# Combined_MXP_board.net
KiCad netlist of a schematic drawn in EAGLE
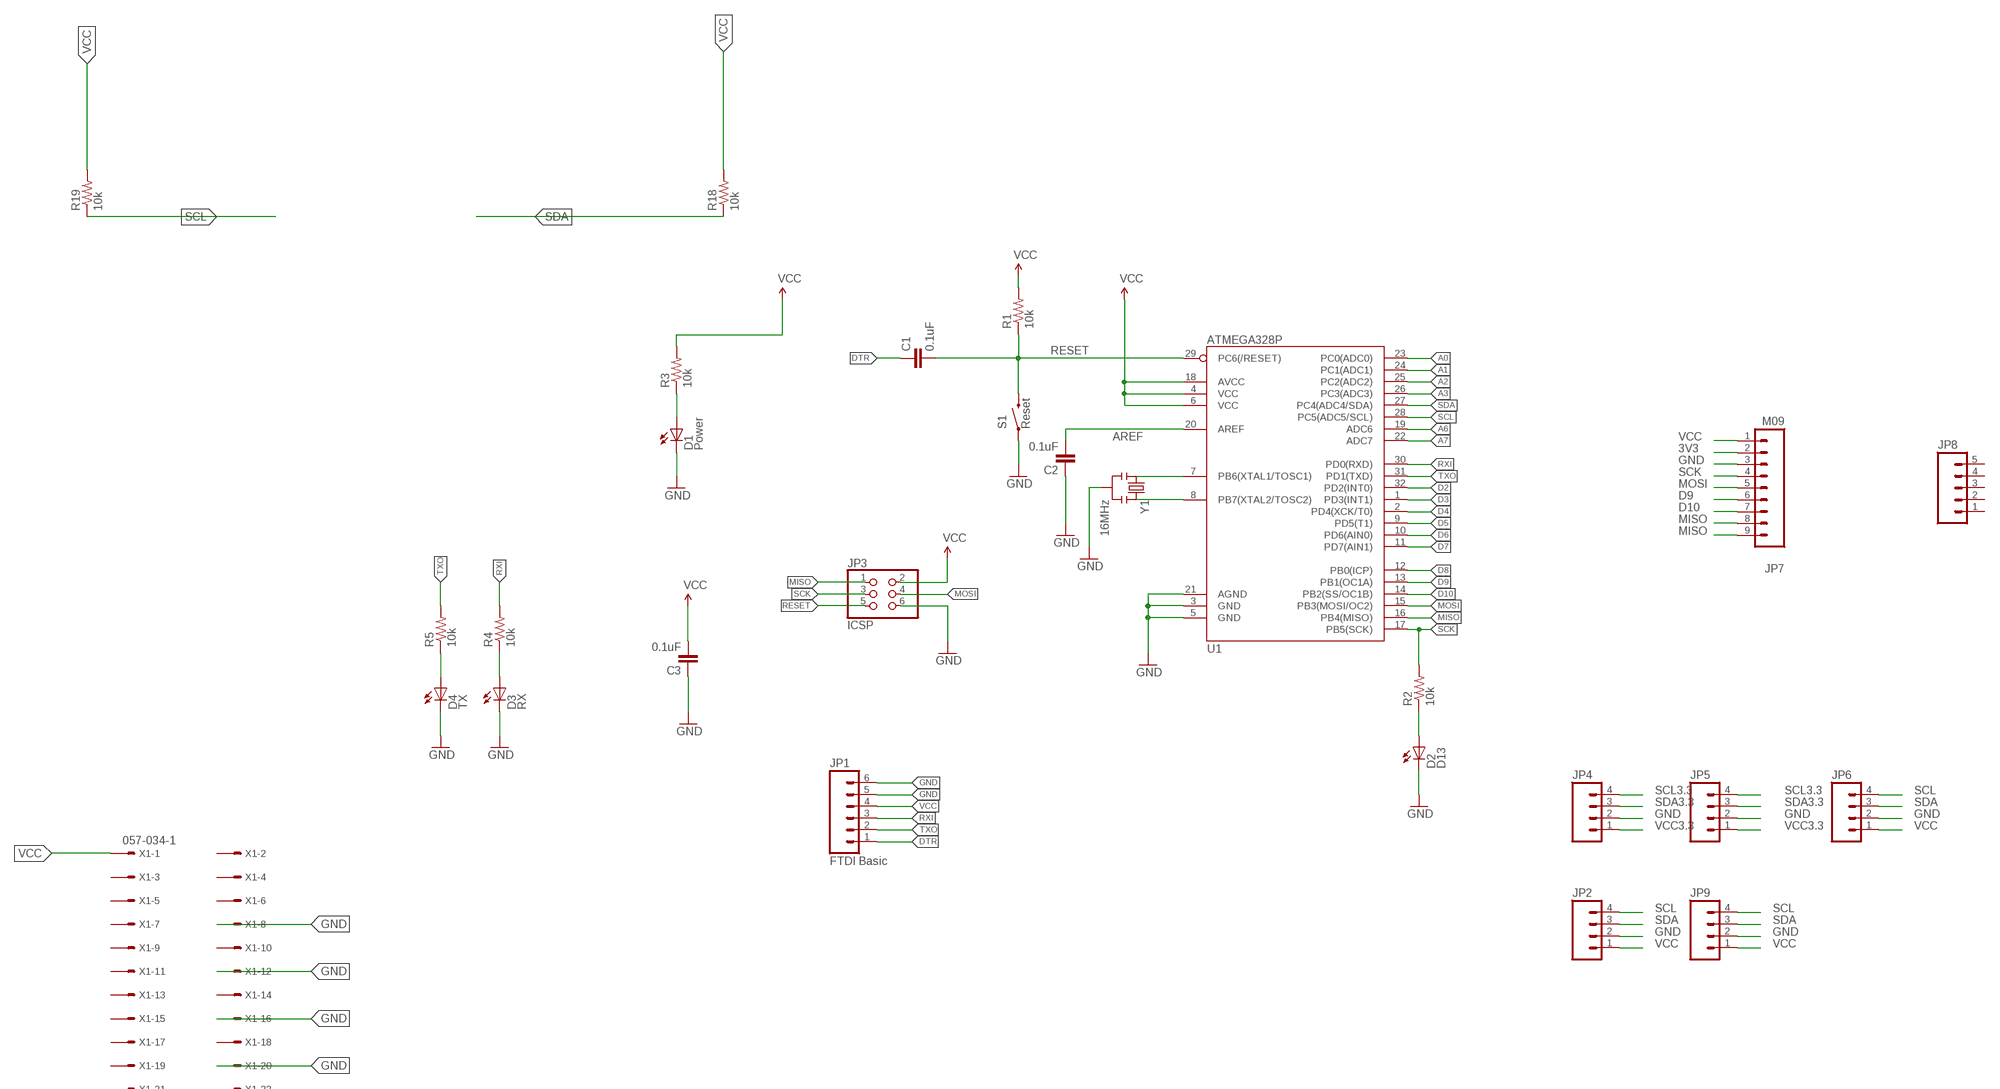
[diagram p0: schematic, sheet 1, part 1 of 2]
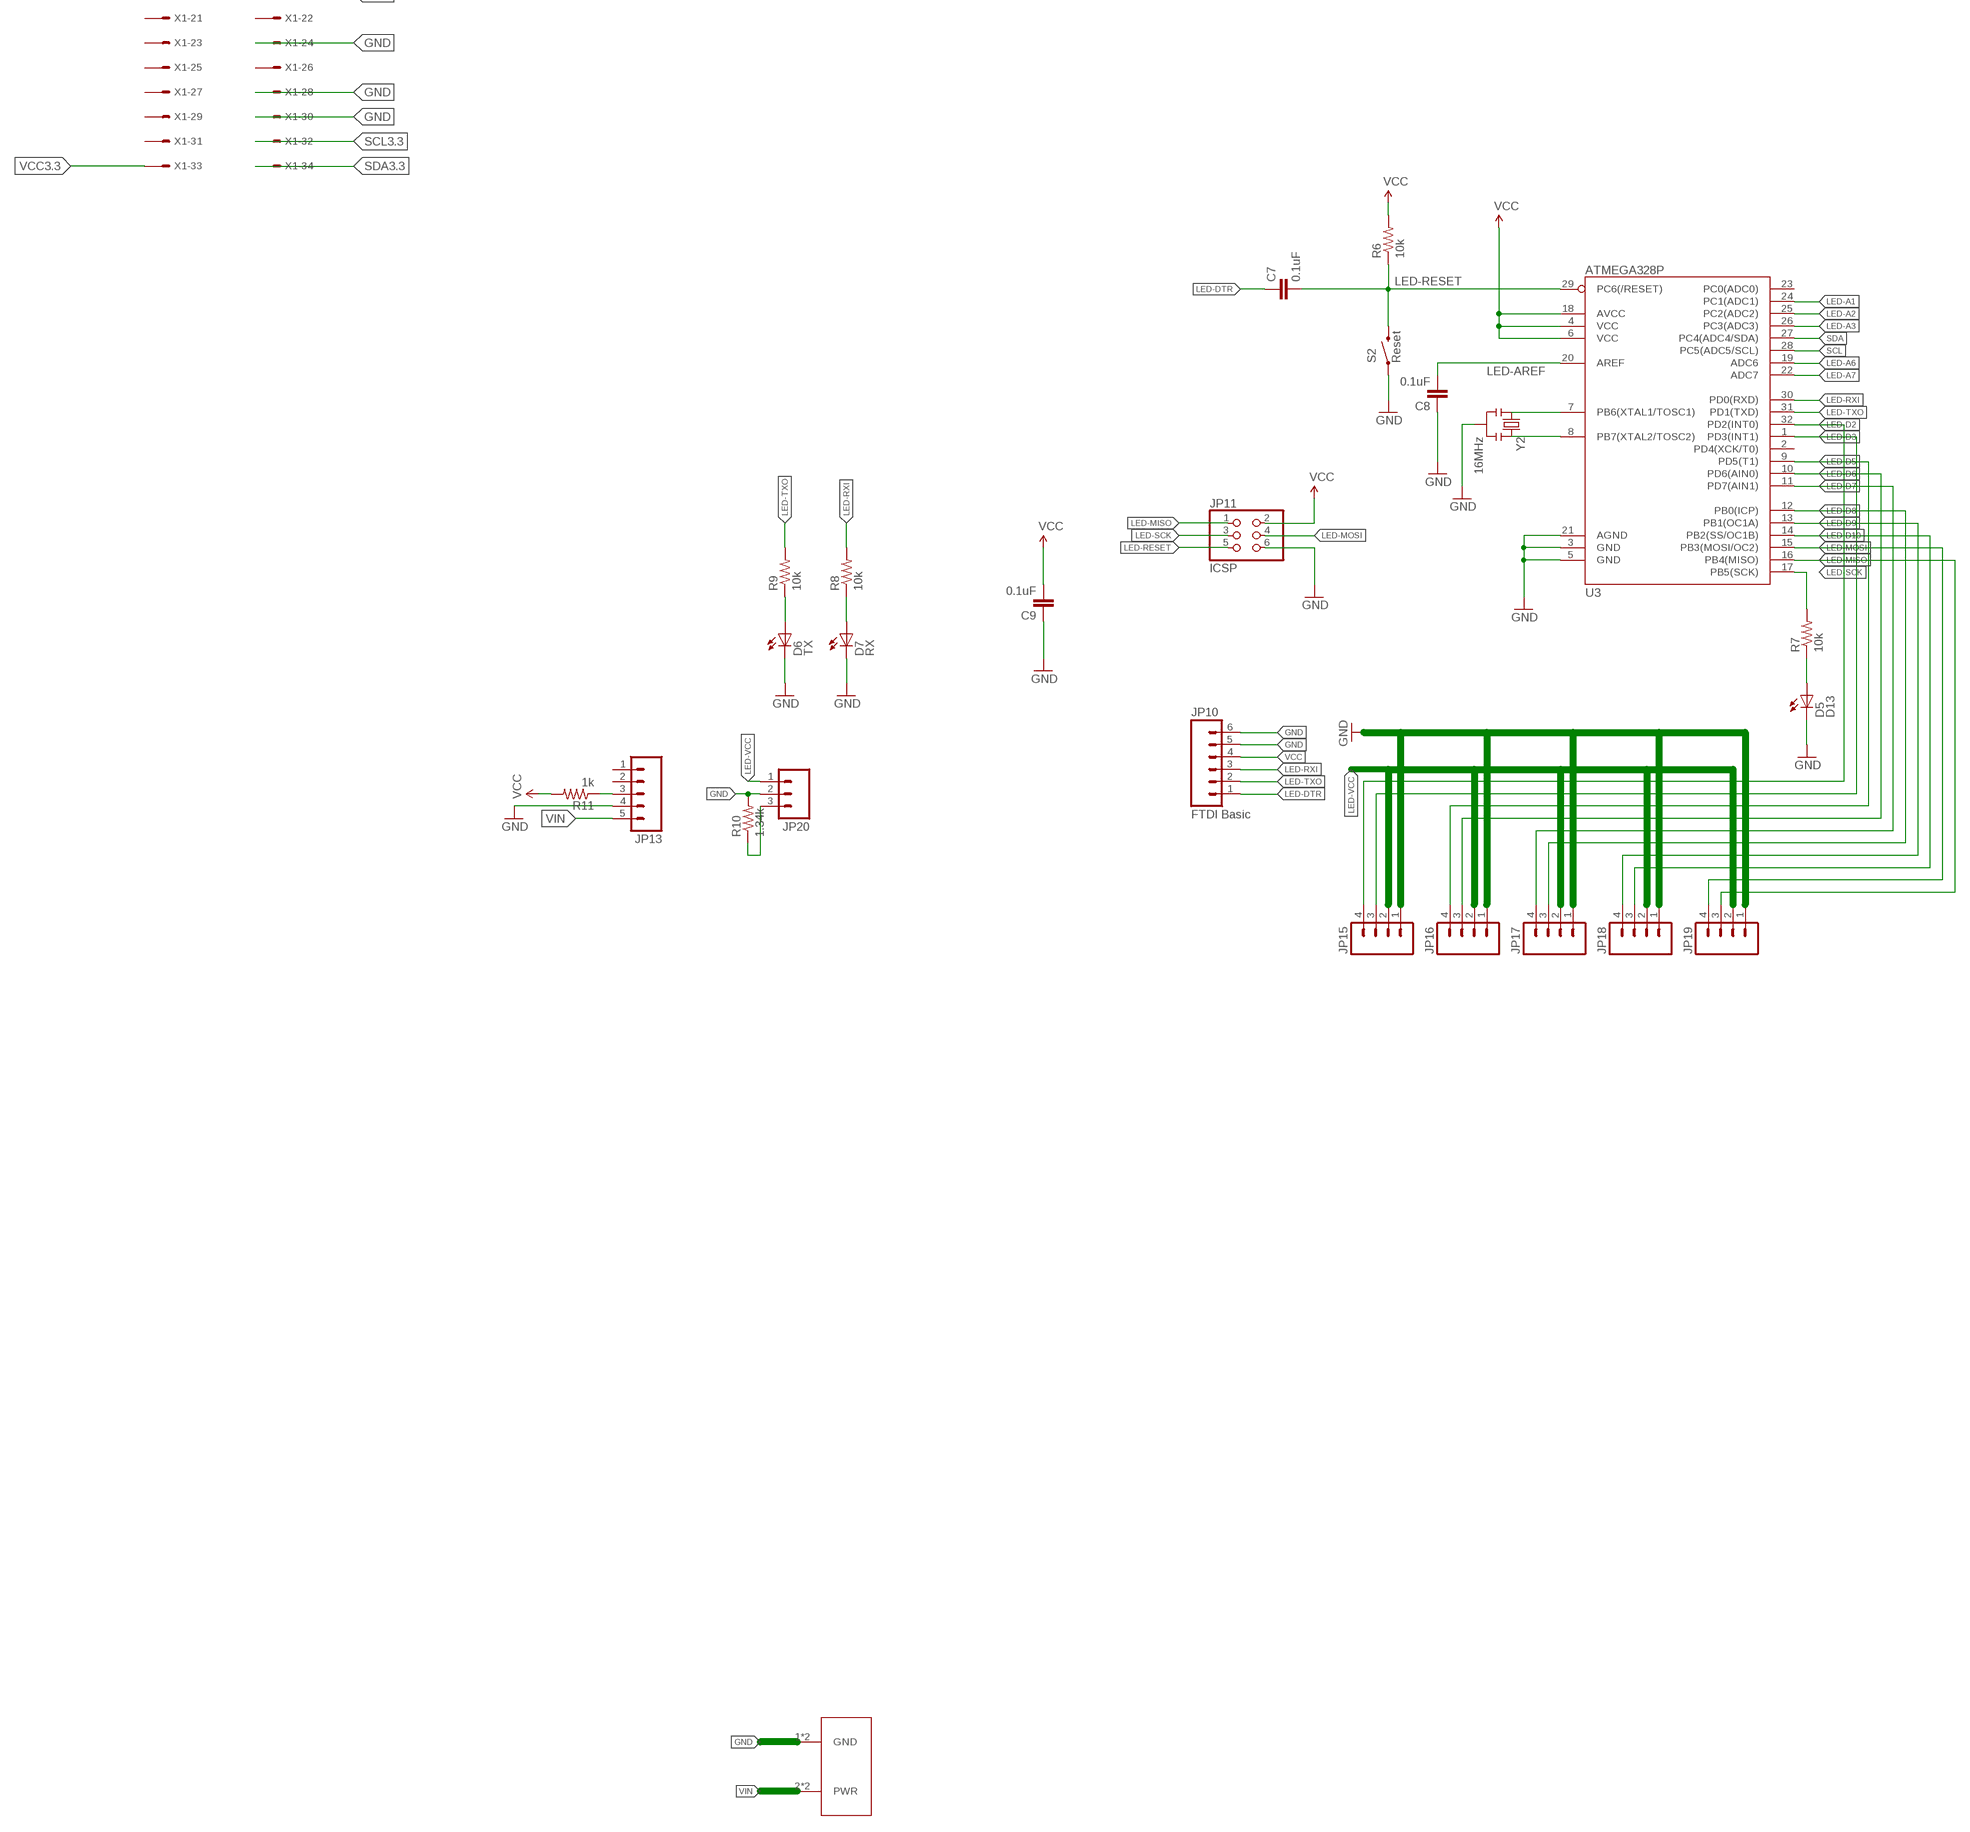
[diagram p1: schematic, sheet 1, part 2 of 2]

(export (version "E")
  (design (tool "Eeschema 10.0.6"))
  (components
    (comp (ref "C1")
      (value "0.1uF")
      (footprint "eagle-import:0603-CAP")
      (libsource (lib "eagle-import") (part "CAP0603-CAP"))
    )
    (comp (ref "C2")
      (value "0.1uF")
      (footprint "eagle-import:0603-CAP")
      (libsource (lib "eagle-import") (part "CAP0603-CAP"))
    )
    (comp (ref "C3")
      (value "0.1uF")
      (footprint "eagle-import:0603-CAP")
      (libsource (lib "eagle-import") (part "CAP0603-CAP"))
    )
    (comp (ref "C7")
      (value "0.1uF")
      (footprint "eagle-import:0603-CAP")
      (libsource (lib "eagle-import") (part "CAP0603-CAP"))
    )
    (comp (ref "C8")
      (value "0.1uF")
      (footprint "eagle-import:0603-CAP")
      (libsource (lib "eagle-import") (part "CAP0603-CAP"))
    )
    (comp (ref "C9")
      (value "0.1uF")
      (footprint "eagle-import:0603-CAP")
      (libsource (lib "eagle-import") (part "CAP0603-CAP"))
    )
    (comp (ref "D1")
      (value "Power")
      (footprint "eagle-import:LED-0603")
      (libsource (lib "eagle-import") (part "LED-RED0603"))
    )
    (comp (ref "D2")
      (value "D13")
      (footprint "eagle-import:LED-0603")
      (libsource (lib "eagle-import") (part "LED-RED0603"))
    )
    (comp (ref "D3")
      (value "RX")
      (footprint "eagle-import:LED-0603")
      (libsource (lib "eagle-import") (part "LED-GREEN0603"))
    )
    (comp (ref "D4")
      (value "TX")
      (footprint "eagle-import:LED-0603")
      (libsource (lib "eagle-import") (part "LED-RED0603"))
    )
    (comp (ref "D5")
      (value "D13")
      (footprint "eagle-import:LED-0603")
      (libsource (lib "eagle-import") (part "LED-RED0603"))
    )
    (comp (ref "D6")
      (value "TX")
      (footprint "eagle-import:LED-0603")
      (libsource (lib "eagle-import") (part "LED-RED0603"))
    )
    (comp (ref "D7")
      (value "RX")
      (footprint "eagle-import:LED-0603")
      (libsource (lib "eagle-import") (part "LED-GREEN0603"))
    )
    (comp (ref "JP1")
      (value "FTDI Basic")
      (footprint "eagle-import:1X06")
      (libsource (lib "eagle-import") (part "M06SIP"))
    )
    (comp (ref "JP2")
      (value "M04PTH")
      (footprint "eagle-import:1X04")
      (libsource (lib "eagle-import") (part "M04PTH"))
    )
    (comp (ref "JP3")
      (value "ICSP")
      (footprint "eagle-import:2X03")
      (libsource (lib "eagle-import") (part "PINHD-2X3"))
    )
    (comp (ref "JP4")
      (value "M04PTH")
      (footprint "eagle-import:1X04")
      (libsource (lib "eagle-import") (part "M04PTH"))
    )
    (comp (ref "JP5")
      (value "M04PTH")
      (footprint "eagle-import:1X04")
      (libsource (lib "eagle-import") (part "M04PTH"))
    )
    (comp (ref "JP6")
      (value "M04PTH")
      (footprint "eagle-import:1X04")
      (libsource (lib "eagle-import") (part "M04PTH"))
    )
    (comp (ref "JP7")
      (value "M09")
      (footprint "eagle-import:1X09")
      (libsource (lib "eagle-import") (part "M09"))
    )
    (comp (ref "JP8")
      (value "M05PTH")
      (footprint "eagle-import:1X05")
      (libsource (lib "eagle-import") (part "M05PTH"))
    )
    (comp (ref "JP9")
      (value "M04PTH")
      (footprint "eagle-import:1X04")
      (libsource (lib "eagle-import") (part "M04PTH"))
    )
    (comp (ref "JP10")
      (value "FTDI Basic")
      (footprint "eagle-import:1X06")
      (libsource (lib "eagle-import") (part "M06SIP"))
    )
    (comp (ref "JP11")
      (value "ICSP")
      (footprint "eagle-import:2X03")
      (libsource (lib "eagle-import") (part "PINHD-2X3"))
    )
    (comp (ref "JP13")
      (value "M05PTH")
      (footprint "eagle-import:1X05")
      (libsource (lib "eagle-import") (part "M05PTH"))
    )
    (comp (ref "JP15")
      (value "M04PTH")
      (footprint "eagle-import:1X04")
      (libsource (lib "eagle-import") (part "M04PTH"))
    )
    (comp (ref "JP16")
      (value "M04PTH")
      (footprint "eagle-import:1X04")
      (libsource (lib "eagle-import") (part "M04PTH"))
    )
    (comp (ref "JP17")
      (value "M04PTH")
      (footprint "eagle-import:1X04")
      (libsource (lib "eagle-import") (part "M04PTH"))
    )
    (comp (ref "JP18")
      (value "M04PTH")
      (footprint "eagle-import:1X04")
      (libsource (lib "eagle-import") (part "M04PTH"))
    )
    (comp (ref "JP19")
      (value "M04PTH")
      (footprint "eagle-import:1X04")
      (libsource (lib "eagle-import") (part "M04PTH"))
    )
    (comp (ref "JP20")
      (value "M03PTH")
      (footprint "eagle-import:1X03")
      (libsource (lib "eagle-import") (part "M03PTH"))
    )
    (comp (ref "R1")
      (value "10k")
      (footprint "eagle-import:0603-RES")
      (libsource (lib "eagle-import") (part "RESISTOR0603-RES"))
    )
    (comp (ref "R2")
      (value "10k")
      (footprint "eagle-import:0603-RES")
      (libsource (lib "eagle-import") (part "RESISTOR0603-RES"))
    )
    (comp (ref "R3")
      (value "10k")
      (footprint "eagle-import:0603-RES")
      (libsource (lib "eagle-import") (part "RESISTOR0603-RES"))
    )
    (comp (ref "R4")
      (value "10k")
      (footprint "eagle-import:0603-RES")
      (libsource (lib "eagle-import") (part "RESISTOR0603-RES"))
    )
    (comp (ref "R5")
      (value "10k")
      (footprint "eagle-import:0603-RES")
      (libsource (lib "eagle-import") (part "RESISTOR0603-RES"))
    )
    (comp (ref "R6")
      (value "10k")
      (footprint "eagle-import:0603-RES")
      (libsource (lib "eagle-import") (part "RESISTOR0603-RES"))
    )
    (comp (ref "R7")
      (value "10k")
      (footprint "eagle-import:0603-RES")
      (libsource (lib "eagle-import") (part "RESISTOR0603-RES"))
    )
    (comp (ref "R8")
      (value "10k")
      (footprint "eagle-import:0603-RES")
      (libsource (lib "eagle-import") (part "RESISTOR0603-RES"))
    )
    (comp (ref "R9")
      (value "10k")
      (footprint "eagle-import:0603-RES")
      (libsource (lib "eagle-import") (part "RESISTOR0603-RES"))
    )
    (comp (ref "R10")
      (value "1.34k")
      (footprint "eagle-import:AXIAL-0.3")
      (libsource (lib "eagle-import") (part "SparkFun-Resistors_RESISTORAXIAL-0.3"))
    )
    (comp (ref "R11")
      (value "1k")
      (footprint "eagle-import:AXIAL-0.3")
      (libsource (lib "eagle-import") (part "SparkFun-Resistors_RESISTORAXIAL-0.3"))
    )
    (comp (ref "R18")
      (value "10k")
      (footprint "eagle-import:0603-RES")
      (libsource (lib "eagle-import") (part "RESISTOR0603-RES"))
    )
    (comp (ref "R19")
      (value "10k")
      (footprint "eagle-import:0603-RES")
      (libsource (lib "eagle-import") (part "RESISTOR0603-RES"))
    )
    (comp (ref "S1")
      (value "Reset")
      (footprint "eagle-import:TACTILE_SWITCH_SMD")
      (libsource (lib "eagle-import") (part "SWITCH-MOMENTARY-2SMD"))
    )
    (comp (ref "S2")
      (value "Reset")
      (footprint "eagle-import:TACTILE_SWITCH_SMD")
      (libsource (lib "eagle-import") (part "SWITCH-MOMENTARY-2SMD"))
    )
    (comp (ref "U$2")
      (value "LSF-SMT")
      (footprint "eagle-import:LSF-SMT")
      (libsource (lib "eagle-import") (part "LSF-SMT"))
    )
    (comp (ref "U1")
      (value "ATMEGA328P")
      (footprint "eagle-import:TQFP32-08")
      (libsource (lib "eagle-import") (part "ATMEGA328_SMT"))
    )
    (comp (ref "U3")
      (value "ATMEGA328P")
      (footprint "eagle-import:TQFP32-08")
      (libsource (lib "eagle-import") (part "ATMEGA328_SMT"))
    )
    (comp (ref "X1")
      (value "057-034-1")
      (footprint "eagle-import:057-034-1")
      (libsource (lib "eagle-import") (part "057-034-1"))
    )
    (comp (ref "Y1")
      (value "16MHz")
      (footprint "eagle-import:RESONATOR-SMD")
      (libsource (lib "eagle-import") (part "RESONATOR16MHZ"))
    )
    (comp (ref "Y2")
      (value "16MHz")
      (footprint "eagle-import:RESONATOR-SMD")
      (libsource (lib "eagle-import") (part "RESONATOR16MHZ"))
    )
  )
  (nets
    (net (code "1") (name "/3V3") (class "Default")
      (node (ref "JP7") (pin "2") (pinfunction "2_2") (pintype "passive"))
    )
    (net (code "2") (name "/AREF") (class "Default")
      (node (ref "C2") (pin "2") (pinfunction "2_2") (pintype "passive"))
      (node (ref "U1") (pin "20") (pinfunction "AREF_20") (pintype "bidirectional"))
    )
    (net (code "3") (name "/LED-AREF") (class "Default")
      (node (ref "C8") (pin "2") (pinfunction "2_2") (pintype "passive"))
      (node (ref "U3") (pin "20") (pinfunction "AREF_20") (pintype "bidirectional"))
    )
    (net (code "4") (name "A0") (class "Default")
      (node (ref "U1") (pin "23") (pinfunction "PC0(ADC0)_23") (pintype "bidirectional"))
    )
    (net (code "5") (name "A1") (class "Default")
      (node (ref "U1") (pin "24") (pinfunction "PC1(ADC1)_24") (pintype "bidirectional"))
    )
    (net (code "6") (name "A2") (class "Default")
      (node (ref "U1") (pin "25") (pinfunction "PC2(ADC2)_25") (pintype "bidirectional"))
    )
    (net (code "7") (name "A3") (class "Default")
      (node (ref "U1") (pin "26") (pinfunction "PC3(ADC3)_26") (pintype "bidirectional"))
    )
    (net (code "8") (name "A6") (class "Default")
      (node (ref "U1") (pin "19") (pinfunction "ADC6_19") (pintype "bidirectional"))
    )
    (net (code "9") (name "A7") (class "Default")
      (node (ref "U1") (pin "22") (pinfunction "ADC7_22") (pintype "bidirectional"))
    )
    (net (code "10") (name "D2") (class "Default")
      (node (ref "U1") (pin "32") (pinfunction "PD2(INT0)_32") (pintype "bidirectional"))
    )
    (net (code "11") (name "D3") (class "Default")
      (node (ref "U1") (pin "1") (pinfunction "PD3(INT1)_1") (pintype "bidirectional"))
    )
    (net (code "12") (name "D4") (class "Default")
      (node (ref "U1") (pin "2") (pinfunction "PD4(XCK/T0)_2") (pintype "bidirectional"))
    )
    (net (code "13") (name "D5") (class "Default")
      (node (ref "U1") (pin "9") (pinfunction "PD5(T1)_9") (pintype "bidirectional"))
    )
    (net (code "14") (name "D6") (class "Default")
      (node (ref "U1") (pin "10") (pinfunction "PD6(AIN0)_10") (pintype "bidirectional"))
    )
    (net (code "15") (name "D7") (class "Default")
      (node (ref "U1") (pin "11") (pinfunction "PD7(AIN1)_11") (pintype "bidirectional"))
    )
    (net (code "16") (name "D8") (class "Default")
      (node (ref "U1") (pin "12") (pinfunction "PB0(ICP)_12") (pintype "bidirectional"))
    )
    (net (code "17") (name "D9") (class "Default")
      (node (ref "JP7") (pin "6") (pinfunction "6_6") (pintype "passive"))
      (node (ref "U1") (pin "13") (pinfunction "PB1(OC1A)_13") (pintype "bidirectional"))
    )
    (net (code "18") (name "D10") (class "Default")
      (node (ref "JP7") (pin "7") (pinfunction "7_7") (pintype "passive"))
      (node (ref "U1") (pin "14") (pinfunction "PB2(SS/OC1B)_14") (pintype "bidirectional"))
    )
    (net (code "19") (name "DTR") (class "Default")
      (node (ref "C1") (pin "1") (pinfunction "1_1") (pintype "passive"))
      (node (ref "JP1") (pin "1") (pinfunction "1_1") (pintype "passive"))
    )
    (net (code "20") (name "GND") (class "Default")
      (node (ref "C2") (pin "1") (pinfunction "1_1") (pintype "passive"))
      (node (ref "C3") (pin "1") (pinfunction "1_1") (pintype "passive"))
      (node (ref "C8") (pin "1") (pinfunction "1_1") (pintype "passive"))
      (node (ref "C9") (pin "1") (pinfunction "1_1") (pintype "passive"))
      (node (ref "D1") (pin "C") (pinfunction "C_C") (pintype "passive"))
      (node (ref "D2") (pin "C") (pinfunction "C_C") (pintype "passive"))
      (node (ref "D3") (pin "C") (pinfunction "C_C") (pintype "passive"))
      (node (ref "D4") (pin "C") (pinfunction "C_C") (pintype "passive"))
      (node (ref "D5") (pin "C") (pinfunction "C_C") (pintype "passive"))
      (node (ref "D6") (pin "C") (pinfunction "C_C") (pintype "passive"))
      (node (ref "D7") (pin "C") (pinfunction "C_C") (pintype "passive"))
      (node (ref "JP1") (pin "5") (pinfunction "5_5") (pintype "passive"))
      (node (ref "JP1") (pin "6") (pinfunction "6_6") (pintype "passive"))
      (node (ref "JP10") (pin "5") (pinfunction "5_5") (pintype "passive"))
      (node (ref "JP10") (pin "6") (pinfunction "6_6") (pintype "passive"))
      (node (ref "JP11") (pin "6") (pinfunction "6_6") (pintype "passive"))
      (node (ref "JP13") (pin "4") (pinfunction "4_4") (pintype "passive"))
      (node (ref "JP15") (pin "1") (pinfunction "1_1") (pintype "passive"))
      (node (ref "JP16") (pin "1") (pinfunction "1_1") (pintype "passive"))
      (node (ref "JP17") (pin "1") (pinfunction "1_1") (pintype "passive"))
      (node (ref "JP18") (pin "1") (pinfunction "1_1") (pintype "passive"))
      (node (ref "JP19") (pin "1") (pinfunction "1_1") (pintype "passive"))
      (node (ref "JP2") (pin "2") (pinfunction "2_2") (pintype "passive"))
      (node (ref "JP20") (pin "2") (pinfunction "2_2") (pintype "passive"))
      (node (ref "JP3") (pin "6") (pinfunction "6_6") (pintype "passive"))
      (node (ref "JP4") (pin "2") (pinfunction "2_2") (pintype "passive"))
      (node (ref "JP5") (pin "2") (pinfunction "2_2") (pintype "passive"))
      (node (ref "JP6") (pin "2") (pinfunction "2_2") (pintype "passive"))
      (node (ref "JP7") (pin "3") (pinfunction "3_3") (pintype "passive"))
      (node (ref "JP9") (pin "2") (pinfunction "2_2") (pintype "passive"))
      (node (ref "R10") (pin "P$2") (pinfunction "2_P$2") (pintype "passive"))
      (node (ref "S1") (pin "1") (pinfunction "1_1") (pintype "passive"))
      (node (ref "S2") (pin "1") (pinfunction "1_1") (pintype "passive"))
      (node (ref "U$2") (pin "1") (pinfunction "GND_1") (pintype "bidirectional"))
      (node (ref "U$2") (pin "1-2") (pinfunction "GND_1-2") (pintype "bidirectional"))
      (node (ref "U1") (pin "21") (pinfunction "AGND_21") (pintype "bidirectional"))
      (node (ref "U1") (pin "3") (pinfunction "GND_3") (pintype "bidirectional"))
      (node (ref "U1") (pin "5") (pinfunction "GND_5") (pintype "bidirectional"))
      (node (ref "U3") (pin "21") (pinfunction "AGND_21") (pintype "bidirectional"))
      (node (ref "U3") (pin "3") (pinfunction "GND_3") (pintype "bidirectional"))
      (node (ref "U3") (pin "5") (pinfunction "GND_5") (pintype "bidirectional"))
      (node (ref "X1") (pin "12") (pinfunction "S_12") (pintype "passive"))
      (node (ref "X1") (pin "16") (pinfunction "S_16") (pintype "passive"))
      (node (ref "X1") (pin "20") (pinfunction "S_20") (pintype "passive"))
      (node (ref "X1") (pin "24") (pinfunction "S_24") (pintype "passive"))
      (node (ref "X1") (pin "28") (pinfunction "S_28") (pintype "passive"))
      (node (ref "X1") (pin "30") (pinfunction "S_30") (pintype "passive"))
      (node (ref "X1") (pin "8") (pinfunction "S_8") (pintype "passive"))
      (node (ref "Y1") (pin "2") (pinfunction "2_2") (pintype "passive"))
      (node (ref "Y2") (pin "2") (pinfunction "2_2") (pintype "passive"))
    )
    (net (code "21") (name "LED-A1") (class "Default")
      (node (ref "U3") (pin "24") (pinfunction "PC1(ADC1)_24") (pintype "bidirectional"))
    )
    (net (code "22") (name "LED-A2") (class "Default")
      (node (ref "U3") (pin "25") (pinfunction "PC2(ADC2)_25") (pintype "bidirectional"))
    )
    (net (code "23") (name "LED-A3") (class "Default")
      (node (ref "U3") (pin "26") (pinfunction "PC3(ADC3)_26") (pintype "bidirectional"))
    )
    (net (code "24") (name "LED-A6") (class "Default")
      (node (ref "U3") (pin "19") (pinfunction "ADC6_19") (pintype "bidirectional"))
    )
    (net (code "25") (name "LED-A7") (class "Default")
      (node (ref "U3") (pin "22") (pinfunction "ADC7_22") (pintype "bidirectional"))
    )
    (net (code "26") (name "LED-D2") (class "Default")
      (node (ref "JP15") (pin "4") (pinfunction "4_4") (pintype "passive"))
      (node (ref "U3") (pin "32") (pinfunction "PD2(INT0)_32") (pintype "bidirectional"))
    )
    (net (code "27") (name "LED-D3") (class "Default")
      (node (ref "JP15") (pin "3") (pinfunction "3_3") (pintype "passive"))
      (node (ref "U3") (pin "1") (pinfunction "PD3(INT1)_1") (pintype "bidirectional"))
    )
    (net (code "28") (name "LED-D5") (class "Default")
      (node (ref "JP16") (pin "4") (pinfunction "4_4") (pintype "passive"))
      (node (ref "U3") (pin "9") (pinfunction "PD5(T1)_9") (pintype "bidirectional"))
    )
    (net (code "29") (name "LED-D6") (class "Default")
      (node (ref "JP16") (pin "3") (pinfunction "3_3") (pintype "passive"))
      (node (ref "U3") (pin "10") (pinfunction "PD6(AIN0)_10") (pintype "bidirectional"))
    )
    (net (code "30") (name "LED-D7") (class "Default")
      (node (ref "JP17") (pin "4") (pinfunction "4_4") (pintype "passive"))
      (node (ref "U3") (pin "11") (pinfunction "PD7(AIN1)_11") (pintype "bidirectional"))
    )
    (net (code "31") (name "LED-D8") (class "Default")
      (node (ref "JP17") (pin "3") (pinfunction "3_3") (pintype "passive"))
      (node (ref "U3") (pin "12") (pinfunction "PB0(ICP)_12") (pintype "bidirectional"))
    )
    (net (code "32") (name "LED-D9") (class "Default")
      (node (ref "JP18") (pin "4") (pinfunction "4_4") (pintype "passive"))
      (node (ref "U3") (pin "13") (pinfunction "PB1(OC1A)_13") (pintype "bidirectional"))
    )
    (net (code "33") (name "LED-D10") (class "Default")
      (node (ref "JP18") (pin "3") (pinfunction "3_3") (pintype "passive"))
      (node (ref "U3") (pin "14") (pinfunction "PB2(SS/OC1B)_14") (pintype "bidirectional"))
    )
    (net (code "34") (name "LED-DTR") (class "Default")
      (node (ref "C7") (pin "1") (pinfunction "1_1") (pintype "passive"))
      (node (ref "JP10") (pin "1") (pinfunction "1_1") (pintype "passive"))
    )
    (net (code "35") (name "LED-MISO") (class "Default")
      (node (ref "JP11") (pin "1") (pinfunction "1_1") (pintype "passive"))
      (node (ref "JP19") (pin "3") (pinfunction "3_3") (pintype "passive"))
      (node (ref "U3") (pin "16") (pinfunction "PB4(MISO)_16") (pintype "bidirectional"))
    )
    (net (code "36") (name "LED-MOSI") (class "Default")
      (node (ref "JP11") (pin "4") (pinfunction "4_4") (pintype "passive"))
      (node (ref "JP19") (pin "4") (pinfunction "4_4") (pintype "passive"))
      (node (ref "U3") (pin "15") (pinfunction "PB3(MOSI/OC2)_15") (pintype "bidirectional"))
    )
    (net (code "37") (name "LED-RESET") (class "Default")
      (node (ref "C7") (pin "2") (pinfunction "2_2") (pintype "passive"))
      (node (ref "JP11") (pin "5") (pinfunction "5_5") (pintype "passive"))
      (node (ref "R6") (pin "1") (pinfunction "1_1") (pintype "passive"))
      (node (ref "S2") (pin "3") (pinfunction "2_3") (pintype "passive"))
      (node (ref "U3") (pin "29") (pinfunction "PC6(/RESET)_29") (pintype "bidirectional"))
    )
    (net (code "38") (name "LED-RXI") (class "Default")
      (node (ref "JP10") (pin "3") (pinfunction "3_3") (pintype "passive"))
      (node (ref "R8") (pin "2") (pinfunction "2_2") (pintype "passive"))
      (node (ref "U3") (pin "30") (pinfunction "PD0(RXD)_30") (pintype "bidirectional"))
    )
    (net (code "39") (name "LED-SCK") (class "Default")
      (node (ref "JP11") (pin "3") (pinfunction "3_3") (pintype "passive"))
      (node (ref "R7") (pin "2") (pinfunction "2_2") (pintype "passive"))
      (node (ref "U3") (pin "17") (pinfunction "PB5(SCK)_17") (pintype "bidirectional"))
    )
    (net (code "40") (name "LED-TXO") (class "Default")
      (node (ref "JP10") (pin "2") (pinfunction "2_2") (pintype "passive"))
      (node (ref "R9") (pin "2") (pinfunction "2_2") (pintype "passive"))
      (node (ref "U3") (pin "31") (pinfunction "PD1(TXD)_31") (pintype "bidirectional"))
    )
    (net (code "41") (name "LED-VCC") (class "Default")
      (node (ref "JP15") (pin "2") (pinfunction "2_2") (pintype "passive"))
      (node (ref "JP16") (pin "2") (pinfunction "2_2") (pintype "passive"))
      (node (ref "JP17") (pin "2") (pinfunction "2_2") (pintype "passive"))
      (node (ref "JP18") (pin "2") (pinfunction "2_2") (pintype "passive"))
      (node (ref "JP19") (pin "2") (pinfunction "2_2") (pintype "passive"))
      (node (ref "JP20") (pin "1") (pinfunction "1_1") (pintype "passive"))
    )
    (net (code "42") (name "MISO") (class "Default")
      (node (ref "JP3") (pin "1") (pinfunction "1_1") (pintype "passive"))
      (node (ref "JP7") (pin "8") (pinfunction "8_8") (pintype "passive"))
      (node (ref "JP7") (pin "9") (pinfunction "9_9") (pintype "passive"))
      (node (ref "U1") (pin "16") (pinfunction "PB4(MISO)_16") (pintype "bidirectional"))
    )
    (net (code "43") (name "MOSI") (class "Default")
      (node (ref "JP3") (pin "4") (pinfunction "4_4") (pintype "passive"))
      (node (ref "JP7") (pin "5") (pinfunction "5_5") (pintype "passive"))
      (node (ref "U1") (pin "15") (pinfunction "PB3(MOSI/OC2)_15") (pintype "bidirectional"))
    )
    (net (code "44") (name "Net-(D1-PadA)") (class "Default")
      (node (ref "D1") (pin "A") (pinfunction "A_A") (pintype "passive"))
      (node (ref "R3") (pin "1") (pinfunction "1_1") (pintype "passive"))
    )
    (net (code "45") (name "Net-(D2-PadA)") (class "Default")
      (node (ref "D2") (pin "A") (pinfunction "A_A") (pintype "passive"))
      (node (ref "R2") (pin "1") (pinfunction "1_1") (pintype "passive"))
    )
    (net (code "46") (name "Net-(D3-PadA)") (class "Default")
      (node (ref "D3") (pin "A") (pinfunction "A_A") (pintype "passive"))
      (node (ref "R4") (pin "1") (pinfunction "1_1") (pintype "passive"))
    )
    (net (code "47") (name "Net-(D4-PadA)") (class "Default")
      (node (ref "D4") (pin "A") (pinfunction "A_A") (pintype "passive"))
      (node (ref "R5") (pin "1") (pinfunction "1_1") (pintype "passive"))
    )
    (net (code "48") (name "Net-(D5-PadA)") (class "Default")
      (node (ref "D5") (pin "A") (pinfunction "A_A") (pintype "passive"))
      (node (ref "R7") (pin "1") (pinfunction "1_1") (pintype "passive"))
    )
    (net (code "49") (name "Net-(D6-PadA)") (class "Default")
      (node (ref "D6") (pin "A") (pinfunction "A_A") (pintype "passive"))
      (node (ref "R9") (pin "1") (pinfunction "1_1") (pintype "passive"))
    )
    (net (code "50") (name "Net-(D7-PadA)") (class "Default")
      (node (ref "D7") (pin "A") (pinfunction "A_A") (pintype "passive"))
      (node (ref "R8") (pin "1") (pinfunction "1_1") (pintype "passive"))
    )
    (net (code "51") (name "Net-(R10-1)") (class "Default")
      (node (ref "JP20") (pin "3") (pinfunction "3_3") (pintype "passive"))
      (node (ref "R10") (pin "P$1") (pinfunction "1_P$1") (pintype "passive"))
    )
    (net (code "52") (name "Net-(R11-1)") (class "Default")
      (node (ref "JP13") (pin "3") (pinfunction "3_3") (pintype "passive"))
      (node (ref "R11") (pin "P$1") (pinfunction "1_P$1") (pintype "passive"))
    )
    (net (code "53") (name "Net-(U1-PB6(XTAL1{slash}TOSC1))") (class "Default")
      (node (ref "U1") (pin "7") (pinfunction "PB6(XTAL1/TOSC1)_7") (pintype "bidirectional"))
      (node (ref "Y1") (pin "1") (pinfunction "1_1") (pintype "passive"))
    )
    (net (code "54") (name "Net-(U1-PB7(XTAL2{slash}TOSC2))") (class "Default")
      (node (ref "U1") (pin "8") (pinfunction "PB7(XTAL2/TOSC2)_8") (pintype "bidirectional"))
      (node (ref "Y1") (pin "3") (pinfunction "3_3") (pintype "passive"))
    )
    (net (code "55") (name "Net-(U3-PB6(XTAL1{slash}TOSC1))") (class "Default")
      (node (ref "U3") (pin "7") (pinfunction "PB6(XTAL1/TOSC1)_7") (pintype "bidirectional"))
      (node (ref "Y2") (pin "1") (pinfunction "1_1") (pintype "passive"))
    )
    (net (code "56") (name "Net-(U3-PB7(XTAL2{slash}TOSC2))") (class "Default")
      (node (ref "U3") (pin "8") (pinfunction "PB7(XTAL2/TOSC2)_8") (pintype "bidirectional"))
      (node (ref "Y2") (pin "3") (pinfunction "3_3") (pintype "passive"))
    )
    (net (code "57") (name "RESET") (class "Default")
      (node (ref "C1") (pin "2") (pinfunction "2_2") (pintype "passive"))
      (node (ref "JP3") (pin "5") (pinfunction "5_5") (pintype "passive"))
      (node (ref "R1") (pin "1") (pinfunction "1_1") (pintype "passive"))
      (node (ref "S1") (pin "3") (pinfunction "2_3") (pintype "passive"))
      (node (ref "U1") (pin "29") (pinfunction "PC6(/RESET)_29") (pintype "bidirectional"))
    )
    (net (code "58") (name "RXI") (class "Default")
      (node (ref "JP1") (pin "3") (pinfunction "3_3") (pintype "passive"))
      (node (ref "R4") (pin "2") (pinfunction "2_2") (pintype "passive"))
      (node (ref "U1") (pin "30") (pinfunction "PD0(RXD)_30") (pintype "bidirectional"))
    )
    (net (code "59") (name "SCK") (class "Default")
      (node (ref "JP3") (pin "3") (pinfunction "3_3") (pintype "passive"))
      (node (ref "JP7") (pin "4") (pinfunction "4_4") (pintype "passive"))
      (node (ref "R2") (pin "2") (pinfunction "2_2") (pintype "passive"))
      (node (ref "U1") (pin "17") (pinfunction "PB5(SCK)_17") (pintype "bidirectional"))
    )
    (net (code "60") (name "SCL") (class "Default")
      (node (ref "JP2") (pin "4") (pinfunction "4_4") (pintype "passive"))
      (node (ref "JP6") (pin "4") (pinfunction "4_4") (pintype "passive"))
      (node (ref "JP9") (pin "4") (pinfunction "4_4") (pintype "passive"))
      (node (ref "R19") (pin "1") (pinfunction "1_1") (pintype "passive"))
      (node (ref "U1") (pin "28") (pinfunction "PC5(ADC5/SCL)_28") (pintype "bidirectional"))
      (node (ref "U3") (pin "28") (pinfunction "PC5(ADC5/SCL)_28") (pintype "bidirectional"))
    )
    (net (code "61") (name "SCL3.3") (class "Default")
      (node (ref "JP4") (pin "4") (pinfunction "4_4") (pintype "passive"))
      (node (ref "JP5") (pin "4") (pinfunction "4_4") (pintype "passive"))
      (node (ref "X1") (pin "32") (pinfunction "S_32") (pintype "passive"))
    )
    (net (code "62") (name "SDA") (class "Default")
      (node (ref "JP2") (pin "3") (pinfunction "3_3") (pintype "passive"))
      (node (ref "JP6") (pin "3") (pinfunction "3_3") (pintype "passive"))
      (node (ref "JP9") (pin "3") (pinfunction "3_3") (pintype "passive"))
      (node (ref "R18") (pin "1") (pinfunction "1_1") (pintype "passive"))
      (node (ref "U1") (pin "27") (pinfunction "PC4(ADC4/SDA)_27") (pintype "bidirectional"))
      (node (ref "U3") (pin "27") (pinfunction "PC4(ADC4/SDA)_27") (pintype "bidirectional"))
    )
    (net (code "63") (name "SDA3.3") (class "Default")
      (node (ref "JP4") (pin "3") (pinfunction "3_3") (pintype "passive"))
      (node (ref "JP5") (pin "3") (pinfunction "3_3") (pintype "passive"))
      (node (ref "X1") (pin "34") (pinfunction "S_34") (pintype "passive"))
    )
    (net (code "64") (name "TXO") (class "Default")
      (node (ref "JP1") (pin "2") (pinfunction "2_2") (pintype "passive"))
      (node (ref "R5") (pin "2") (pinfunction "2_2") (pintype "passive"))
      (node (ref "U1") (pin "31") (pinfunction "PD1(TXD)_31") (pintype "bidirectional"))
    )
    (net (code "65") (name "VCC") (class "Default")
      (node (ref "C3") (pin "2") (pinfunction "2_2") (pintype "passive"))
      (node (ref "C9") (pin "2") (pinfunction "2_2") (pintype "passive"))
      (node (ref "JP1") (pin "4") (pinfunction "4_4") (pintype "passive"))
      (node (ref "JP10") (pin "4") (pinfunction "4_4") (pintype "passive"))
      (node (ref "JP11") (pin "2") (pinfunction "2_2") (pintype "passive"))
      (node (ref "JP2") (pin "1") (pinfunction "1_1") (pintype "passive"))
      (node (ref "JP3") (pin "2") (pinfunction "2_2") (pintype "passive"))
      (node (ref "JP6") (pin "1") (pinfunction "1_1") (pintype "passive"))
      (node (ref "JP7") (pin "1") (pinfunction "1_1") (pintype "passive"))
      (node (ref "JP9") (pin "1") (pinfunction "1_1") (pintype "passive"))
      (node (ref "R1") (pin "2") (pinfunction "2_2") (pintype "passive"))
      (node (ref "R11") (pin "P$2") (pinfunction "2_P$2") (pintype "passive"))
      (node (ref "R18") (pin "2") (pinfunction "2_2") (pintype "passive"))
      (node (ref "R19") (pin "2") (pinfunction "2_2") (pintype "passive"))
      (node (ref "R3") (pin "2") (pinfunction "2_2") (pintype "passive"))
      (node (ref "R6") (pin "2") (pinfunction "2_2") (pintype "passive"))
      (node (ref "U1") (pin "18") (pinfunction "AVCC_18") (pintype "bidirectional"))
      (node (ref "U1") (pin "4") (pinfunction "VCC_4") (pintype "bidirectional"))
      (node (ref "U1") (pin "6") (pinfunction "VCC_6") (pintype "bidirectional"))
      (node (ref "U3") (pin "18") (pinfunction "AVCC_18") (pintype "bidirectional"))
      (node (ref "U3") (pin "4") (pinfunction "VCC_4") (pintype "bidirectional"))
      (node (ref "U3") (pin "6") (pinfunction "VCC_6") (pintype "bidirectional"))
      (node (ref "X1") (pin "1") (pinfunction "S_1") (pintype "passive"))
    )
    (net (code "66") (name "VCC3.3") (class "Default")
      (node (ref "JP4") (pin "1") (pinfunction "1_1") (pintype "passive"))
      (node (ref "JP5") (pin "1") (pinfunction "1_1") (pintype "passive"))
      (node (ref "X1") (pin "33") (pinfunction "S_33") (pintype "passive"))
    )
    (net (code "67") (name "VIN") (class "Default")
      (node (ref "JP13") (pin "5") (pinfunction "5_5") (pintype "passive"))
      (node (ref "U$2") (pin "2") (pinfunction "PWR_2") (pintype "bidirectional"))
      (node (ref "U$2") (pin "2-2") (pinfunction "PWR_2-2") (pintype "bidirectional"))
    )
    (net (code "68") (name "unconnected-(JP8-Pad1)") (class "Default")
      (node (ref "JP8") (pin "1") (pinfunction "1_1") (pintype "passive"))
    )
    (net (code "69") (name "unconnected-(JP8-Pad2)") (class "Default")
      (node (ref "JP8") (pin "2") (pinfunction "2_2") (pintype "passive"))
    )
    (net (code "70") (name "unconnected-(JP8-Pad3)") (class "Default")
      (node (ref "JP8") (pin "3") (pinfunction "3_3") (pintype "passive"))
    )
    (net (code "71") (name "unconnected-(JP8-Pad4)") (class "Default")
      (node (ref "JP8") (pin "4") (pinfunction "4_4") (pintype "passive"))
    )
    (net (code "72") (name "unconnected-(JP8-Pad5)") (class "Default")
      (node (ref "JP8") (pin "5") (pinfunction "5_5") (pintype "passive"))
    )
    (net (code "73") (name "unconnected-(JP13-Pad1)") (class "Default")
      (node (ref "JP13") (pin "1") (pinfunction "1_1") (pintype "passive"))
    )
    (net (code "74") (name "unconnected-(JP13-Pad2)") (class "Default")
      (node (ref "JP13") (pin "2") (pinfunction "2_2") (pintype "passive"))
    )
    (net (code "75") (name "unconnected-(U3-PC0(ADC0)-Pad23)") (class "Default")
      (node (ref "U3") (pin "23") (pinfunction "PC0(ADC0)_23") (pintype "bidirectional"))
    )
    (net (code "76") (name "unconnected-(U3-PD4(XCK{slash}T0)-Pad2)") (class "Default")
      (node (ref "U3") (pin "2") (pinfunction "PD4(XCK/T0)_2") (pintype "bidirectional"))
    )
    (net (code "77") (name "unconnected-(X1AC-S-Pad4)") (class "Default")
      (node (ref "X1") (pin "4") (pinfunction "S_4") (pintype "passive"))
    )
    (net (code "78") (name "unconnected-(X1AD-S-Pad5)") (class "Default")
      (node (ref "X1") (pin "5") (pinfunction "S_5") (pintype "passive"))
    )
    (net (code "79") (name "unconnected-(X1AE-S-Pad6)") (class "Default")
      (node (ref "X1") (pin "6") (pinfunction "S_6") (pintype "passive"))
    )
    (net (code "80") (name "unconnected-(X1AF-S-Pad7)") (class "Default")
      (node (ref "X1") (pin "7") (pinfunction "S_7") (pintype "passive"))
    )
    (net (code "81") (name "unconnected-(X1AH-S-Pad9)") (class "Default")
      (node (ref "X1") (pin "9") (pinfunction "S_9") (pintype "passive"))
    )
    (net (code "82") (name "unconnected-(X1B-S-Pad10)") (class "Default")
      (node (ref "X1") (pin "10") (pinfunction "S_10") (pintype "passive"))
    )
    (net (code "83") (name "unconnected-(X1C-S-Pad11)") (class "Default")
      (node (ref "X1") (pin "11") (pinfunction "S_11") (pintype "passive"))
    )
    (net (code "84") (name "unconnected-(X1E-S-Pad13)") (class "Default")
      (node (ref "X1") (pin "13") (pinfunction "S_13") (pintype "passive"))
    )
    (net (code "85") (name "unconnected-(X1F-S-Pad14)") (class "Default")
      (node (ref "X1") (pin "14") (pinfunction "S_14") (pintype "passive"))
    )
    (net (code "86") (name "unconnected-(X1G-S-Pad15)") (class "Default")
      (node (ref "X1") (pin "15") (pinfunction "S_15") (pintype "passive"))
    )
    (net (code "87") (name "unconnected-(X1I-S-Pad17)") (class "Default")
      (node (ref "X1") (pin "17") (pinfunction "S_17") (pintype "passive"))
    )
    (net (code "88") (name "unconnected-(X1J-S-Pad18)") (class "Default")
      (node (ref "X1") (pin "18") (pinfunction "S_18") (pintype "passive"))
    )
    (net (code "89") (name "unconnected-(X1K-S-Pad19)") (class "Default")
      (node (ref "X1") (pin "19") (pinfunction "S_19") (pintype "passive"))
    )
    (net (code "90") (name "unconnected-(X1L-S-Pad2)") (class "Default")
      (node (ref "X1") (pin "2") (pinfunction "S_2") (pintype "passive"))
    )
    (net (code "91") (name "unconnected-(X1N-S-Pad21)") (class "Default")
      (node (ref "X1") (pin "21") (pinfunction "S_21") (pintype "passive"))
    )
    (net (code "92") (name "unconnected-(X1O-S-Pad22)") (class "Default")
      (node (ref "X1") (pin "22") (pinfunction "S_22") (pintype "passive"))
    )
    (net (code "93") (name "unconnected-(X1P-S-Pad23)") (class "Default")
      (node (ref "X1") (pin "23") (pinfunction "S_23") (pintype "passive"))
    )
    (net (code "94") (name "unconnected-(X1R-S-Pad25)") (class "Default")
      (node (ref "X1") (pin "25") (pinfunction "S_25") (pintype "passive"))
    )
    (net (code "95") (name "unconnected-(X1S-S-Pad26)") (class "Default")
      (node (ref "X1") (pin "26") (pinfunction "S_26") (pintype "passive"))
    )
    (net (code "96") (name "unconnected-(X1T-S-Pad27)") (class "Default")
      (node (ref "X1") (pin "27") (pinfunction "S_27") (pintype "passive"))
    )
    (net (code "97") (name "unconnected-(X1V-S-Pad29)") (class "Default")
      (node (ref "X1") (pin "29") (pinfunction "S_29") (pintype "passive"))
    )
    (net (code "98") (name "unconnected-(X1W-S-Pad3)") (class "Default")
      (node (ref "X1") (pin "3") (pinfunction "S_3") (pintype "passive"))
    )
    (net (code "99") (name "unconnected-(X1Y-S-Pad31)") (class "Default")
      (node (ref "X1") (pin "31") (pinfunction "S_31") (pintype "passive"))
    )
  )
)
